# MethaneFlux.net
KiCad netlist of a schematic drawn in EAGLE
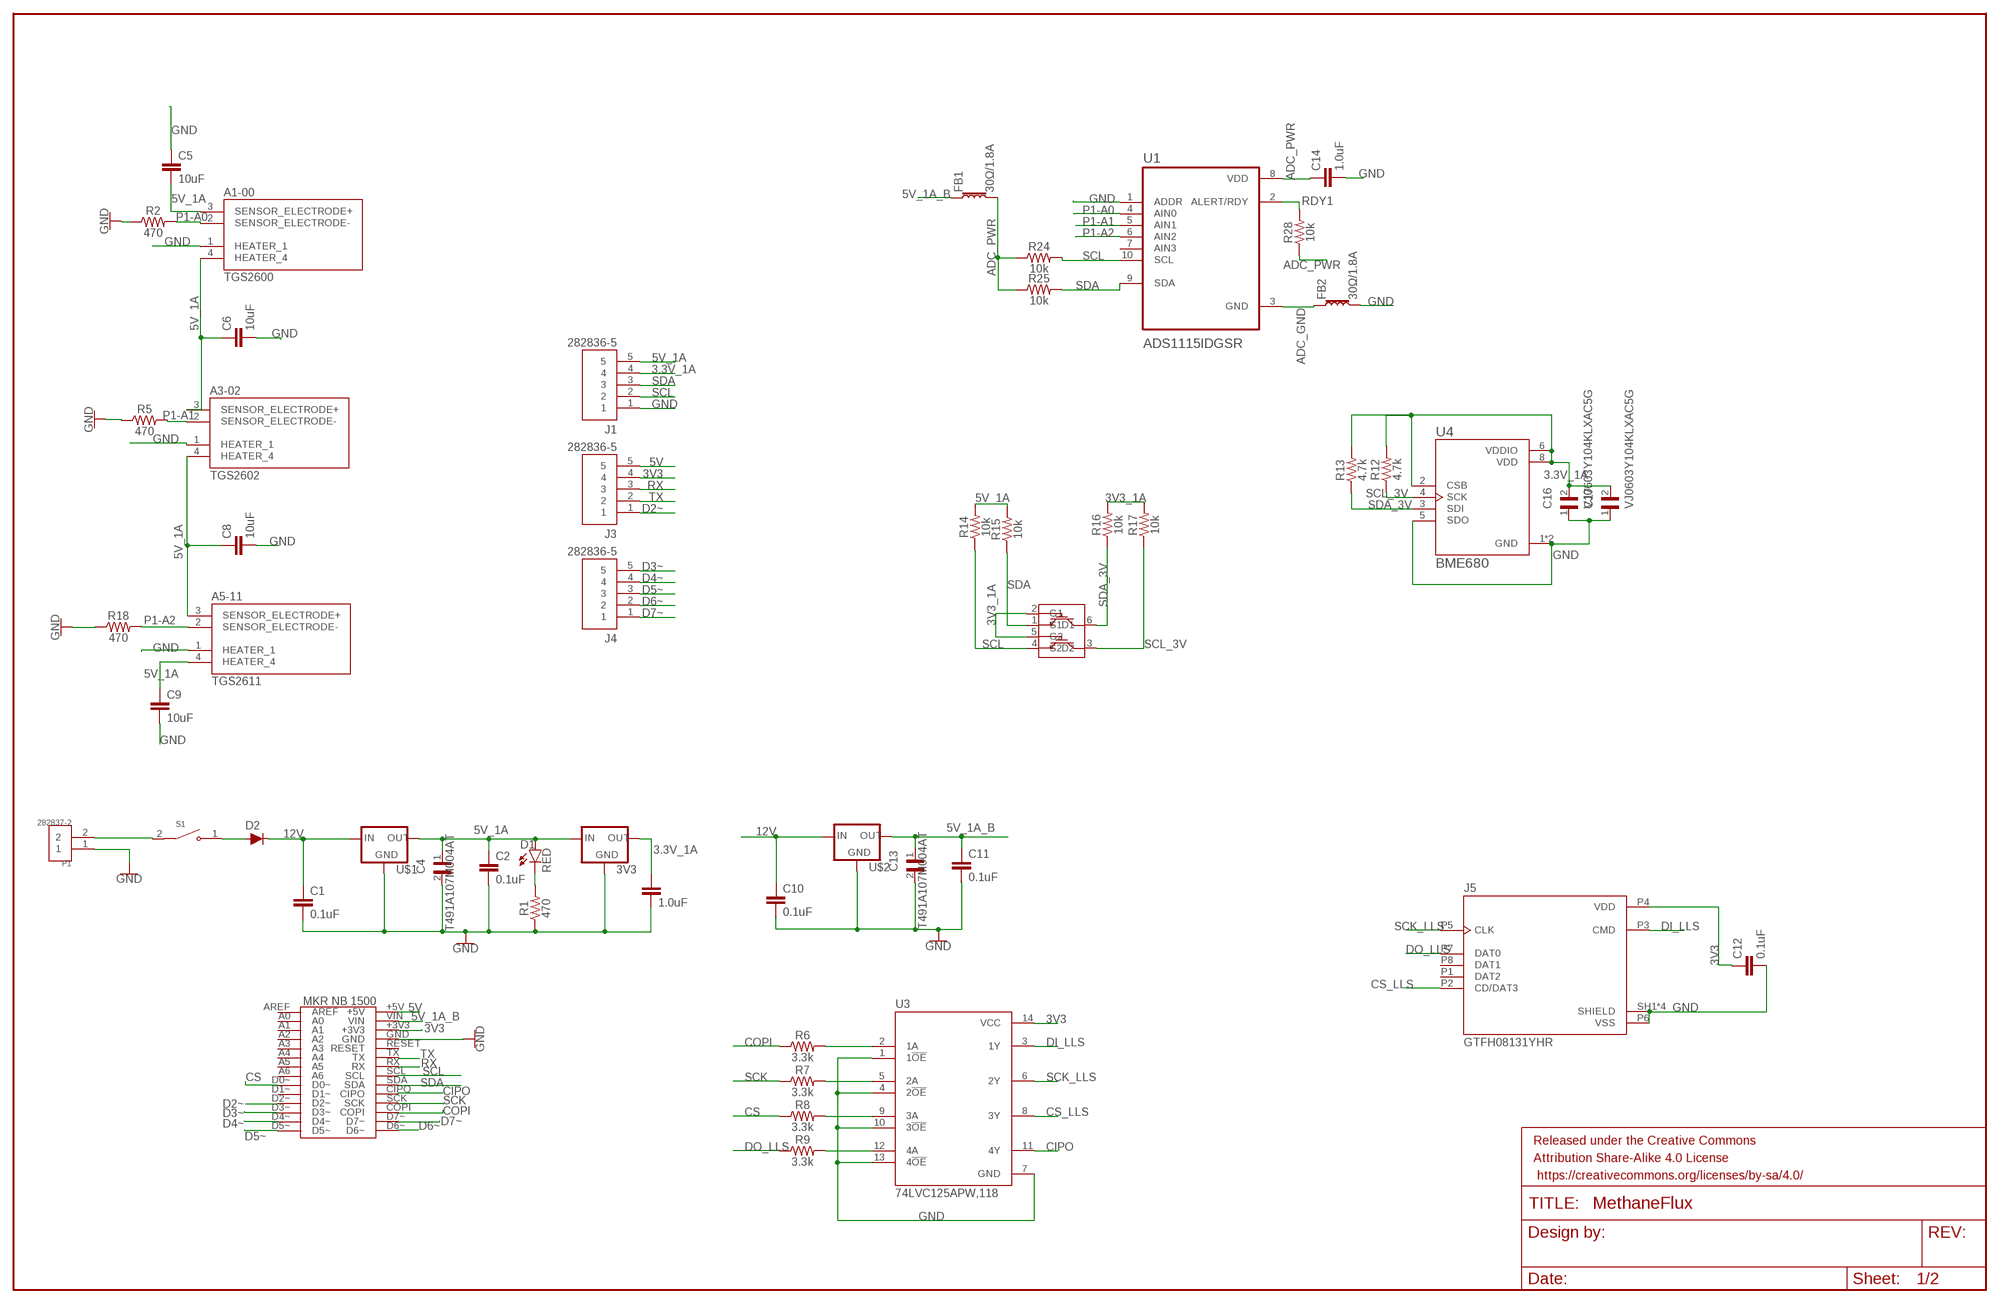
[diagram p0: schematic, sheet 1]
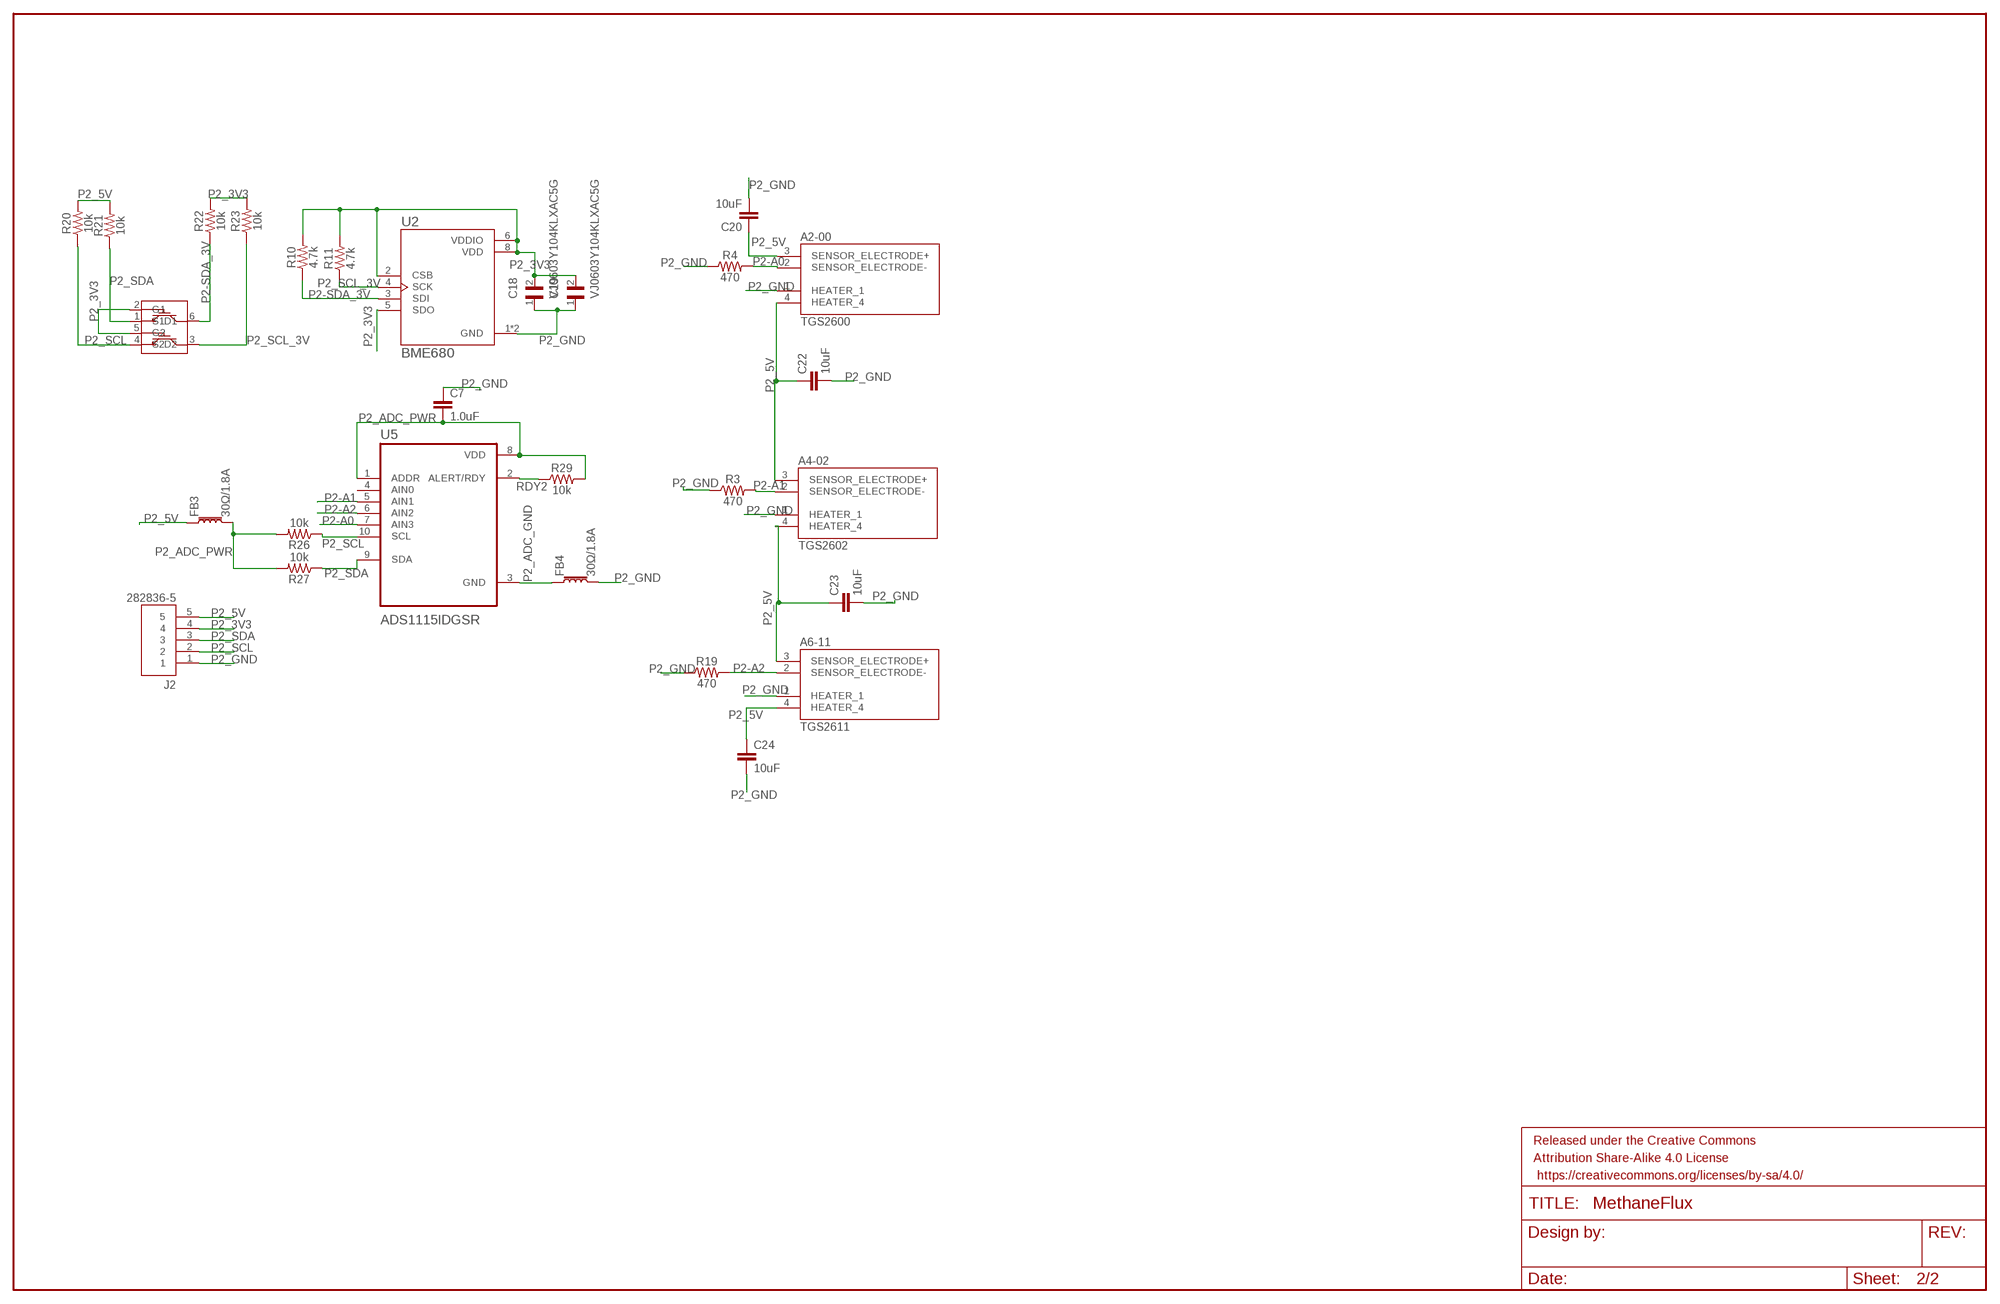
[diagram p1: schematic, sheet 2]

(export (version "E")
  (design (tool "Eeschema 10.0.6"))
  (components
    (comp (ref "3V3")
      (value "V_REG_LD1117VXXLD1117-SMD")
      (footprint "eagle-import:SOT223")
      (libsource (lib "eagle-import") (part "V_REG_LD1117VXXLD1117-SMD"))
    )
    (comp (ref "A1-00")
      (value "TGS2600")
      (footprint "eagle-import:TO255P920H830-4")
      (fields (field (name "MF") "Figaro"))
      (libsource (lib "eagle-import") (part "TGS2600"))
    )
    (comp (ref "A3-02")
      (value "TGS2602")
      (footprint "eagle-import:TGS2602")
      (libsource (lib "eagle-import") (part "TGS2602"))
    )
    (comp (ref "A5-11")
      (value "TGS2611")
      (footprint "eagle-import:TGS2611")
      (libsource (lib "eagle-import") (part "TGS2611"))
    )
    (comp (ref "C1")
      (value "0.1uF")
      (footprint "eagle-import:0603")
      (libsource (lib "eagle-import") (part "0.1UF-0603-25V-5%"))
    )
    (comp (ref "C2")
      (value "0.1uF")
      (footprint "eagle-import:0603")
      (libsource (lib "eagle-import") (part "0.1UF-0603-25V-5%"))
    )
    (comp (ref "C3")
      (value "1.0uF")
      (footprint "eagle-import:0603")
      (libsource (lib "eagle-import") (part "1.0UF-0603-16V-10%"))
    )
    (comp (ref "C4")
      (value "T491A107M004AT")
      (footprint "eagle-import:CAPC3216X110N")
      (fields (field (name "MF") "KEMET"))
      (libsource (lib "eagle-import") (part "T491A107M004AT"))
    )
    (comp (ref "C5")
      (value "10uF")
      (footprint "eagle-import:0603")
      (libsource (lib "eagle-import") (part "10UF-0603-6.3V-20%"))
    )
    (comp (ref "C6")
      (value "10uF")
      (footprint "eagle-import:0603")
      (libsource (lib "eagle-import") (part "10UF-0603-6.3V-20%"))
    )
    (comp (ref "C8")
      (value "10uF")
      (footprint "eagle-import:0603")
      (libsource (lib "eagle-import") (part "10UF-0603-6.3V-20%"))
    )
    (comp (ref "C9")
      (value "10uF")
      (footprint "eagle-import:0603")
      (libsource (lib "eagle-import") (part "10UF-0603-6.3V-20%"))
    )
    (comp (ref "C10")
      (value "0.1uF")
      (footprint "eagle-import:0603")
      (libsource (lib "eagle-import") (part "0.1UF-0603-25V-5%"))
    )
    (comp (ref "C11")
      (value "0.1uF")
      (footprint "eagle-import:0603")
      (libsource (lib "eagle-import") (part "0.1UF-0603-25V-5%"))
    )
    (comp (ref "C12")
      (value "0.1uF")
      (footprint "eagle-import:0603")
      (libsource (lib "eagle-import") (part "0.1UF-0603-25V-5%"))
    )
    (comp (ref "C13")
      (value "T491A107M004AT")
      (footprint "eagle-import:CAPC3216X110N")
      (fields (field (name "MF") "KEMET"))
      (libsource (lib "eagle-import") (part "T491A107M004AT"))
    )
    (comp (ref "C14")
      (value "1.0uF")
      (footprint "eagle-import:0603")
      (libsource (lib "eagle-import") (part "1.0UF-0603-16V-10%"))
    )
    (comp (ref "C16")
      (value "VJ0603Y104KLXAC5G")
      (footprint "eagle-import:CAPC1608X92N")
      (fields (field (name "MF") "Vishay"))
      (libsource (lib "eagle-import") (part "VJ0603Y104KLXAC5G"))
    )
    (comp (ref "C17")
      (value "VJ0603Y104KLXAC5G")
      (footprint "eagle-import:CAPC1608X92N")
      (fields (field (name "MF") "Vishay"))
      (libsource (lib "eagle-import") (part "VJ0603Y104KLXAC5G"))
    )
    (comp (ref "D1")
      (value "RED")
      (footprint "eagle-import:LED-0603")
      (libsource (lib "eagle-import") (part "LED-RED0603"))
    )
    (comp (ref "D2")
      (value "200mA/100V/1V")
      (footprint "eagle-import:DIODE-1N4148")
      (libsource (lib "eagle-import") (part "DIODE-1N4148"))
    )
    (comp (ref "FB1")
      (value "30Ω/1.8A")
      (footprint "eagle-import:0603")
      (libsource (lib "eagle-import") (part "FERRITE_BEAD-0603"))
    )
    (comp (ref "FB2")
      (value "30Ω/1.8A")
      (footprint "eagle-import:0603")
      (libsource (lib "eagle-import") (part "FERRITE_BEAD-0603"))
    )
    (comp (ref "FRAME1")
      (value "FRAME-LEDGER")
      (footprint "eagle-import:CREATIVE_COMMONS")
      (libsource (lib "eagle-import") (part "FRAME-LEDGER"))
    )
    (comp (ref "J1")
      (value "282836-5")
      (footprint "eagle-import:TE_282836-5")
      (fields (field (name "MF") "TE Connectivity"))
      (libsource (lib "eagle-import") (part "282836-5"))
    )
    (comp (ref "J3")
      (value "282836-5")
      (footprint "eagle-import:TE_282836-5")
      (fields (field (name "MF") "TE Connectivity"))
      (libsource (lib "eagle-import") (part "282836-5"))
    )
    (comp (ref "J4")
      (value "282836-5")
      (footprint "eagle-import:TE_282836-5")
      (fields (field (name "MF") "TE Connectivity"))
      (libsource (lib "eagle-import") (part "282836-5"))
    )
    (comp (ref "J5")
      (value "GTFH08131YHR")
      (footprint "eagle-import:AMPHENOL_GTFH08131YHR")
      (fields (field (name "MF") "Amphenol ICC"))
      (libsource (lib "eagle-import") (part "GTFH08131YHR"))
    )
    (comp (ref "P1")
      (value "282837-2")
      (footprint "eagle-import:TE_282837-2")
      (fields (field (name "MF") "TE Connectivity"))
      (libsource (lib "eagle-import") (part "282837-2"))
    )
    (comp (ref "R1")
      (value "470")
      (footprint "eagle-import:0603")
      (libsource (lib "eagle-import") (part "470OHM-0603-1/10W-1%"))
    )
    (comp (ref "R2")
      (value "470")
      (footprint "eagle-import:0603")
      (libsource (lib "eagle-import") (part "470OHM-0603-1/10W-1%"))
    )
    (comp (ref "R5")
      (value "470")
      (footprint "eagle-import:0603")
      (libsource (lib "eagle-import") (part "470OHM-0603-1/10W-1%"))
    )
    (comp (ref "R6")
      (value "3.3k")
      (footprint "eagle-import:0603")
      (libsource (lib "eagle-import") (part "3.3KOHM-0603-1/10W-1%"))
    )
    (comp (ref "R7")
      (value "3.3k")
      (footprint "eagle-import:0603")
      (libsource (lib "eagle-import") (part "3.3KOHM-0603-1/10W-1%"))
    )
    (comp (ref "R8")
      (value "3.3k")
      (footprint "eagle-import:0603")
      (libsource (lib "eagle-import") (part "3.3KOHM-0603-1/10W-1%"))
    )
    (comp (ref "R9")
      (value "3.3k")
      (footprint "eagle-import:0603")
      (libsource (lib "eagle-import") (part "3.3KOHM-0603-1/10W-1%"))
    )
    (comp (ref "R12")
      (value "4.7k")
      (footprint "eagle-import:0603")
      (libsource (lib "eagle-import") (part "4.7KOHM-0603-1/10W-1%"))
    )
    (comp (ref "R13")
      (value "4.7k")
      (footprint "eagle-import:0603")
      (libsource (lib "eagle-import") (part "4.7KOHM-0603-1/10W-1%"))
    )
    (comp (ref "R14")
      (value "10k")
      (footprint "eagle-import:0603")
      (libsource (lib "eagle-import") (part "10KOHM-0603-1/10W-1%"))
    )
    (comp (ref "R15")
      (value "10k")
      (footprint "eagle-import:0603")
      (libsource (lib "eagle-import") (part "10KOHM-0603-1/10W-1%"))
    )
    (comp (ref "R16")
      (value "10k")
      (footprint "eagle-import:0603")
      (libsource (lib "eagle-import") (part "10KOHM-0603-1/10W-1%"))
    )
    (comp (ref "R17")
      (value "10k")
      (footprint "eagle-import:0603")
      (libsource (lib "eagle-import") (part "10KOHM-0603-1/10W-1%"))
    )
    (comp (ref "R18")
      (value "470")
      (footprint "eagle-import:0603")
      (libsource (lib "eagle-import") (part "470OHM-0603-1/10W-1%"))
    )
    (comp (ref "R24")
      (value "10k")
      (footprint "eagle-import:0603")
      (libsource (lib "eagle-import") (part "10KOHM-0603-1/10W-1%"))
    )
    (comp (ref "R25")
      (value "10k")
      (footprint "eagle-import:0603")
      (libsource (lib "eagle-import") (part "10KOHM-0603-1/10W-1%"))
    )
    (comp (ref "R28")
      (value "10k")
      (footprint "eagle-import:0603")
      (libsource (lib "eagle-import") (part "10KOHM-0603-1/10W-1%"))
    )
    (comp (ref "S1")
      (value "RB141C1100")
      (footprint "eagle-import:SW_RB141C1100")
      (fields (field (name "MF") "E-Switch"))
      (libsource (lib "eagle-import") (part "RB141C1100"))
    )
    (comp (ref "U$1")
      (value "V_REG_LD1117VXXLD1117-SMD")
      (footprint "eagle-import:SOT223")
      (libsource (lib "eagle-import") (part "V_REG_LD1117VXXLD1117-SMD"))
    )
    (comp (ref "U$2")
      (value "V_REG_LD1117VXXLD1117-SMD")
      (footprint "eagle-import:SOT223")
      (libsource (lib "eagle-import") (part "V_REG_LD1117VXXLD1117-SMD"))
    )
    (comp (ref "U$3")
      (value "2N7002DW")
      (footprint "eagle-import:SOT363")
      (fields (field (name "MF") "onsemi"))
      (libsource (lib "eagle-import") (part "2N7002DW"))
    )
    (comp (ref "U$5")
      (value "MKRNB1500")
      (footprint "eagle-import:MRKNB1500")
      (libsource (lib "eagle-import") (part "MKRNB1500"))
    )
    (comp (ref "U1")
      (value "ADS1115IDGSR")
      (footprint "eagle-import:SOP50P490X110-10N")
      (fields (field (name "MF") "Texas Instruments"))
      (libsource (lib "eagle-import") (part "ADS1115IDGSR"))
    )
    (comp (ref "U3")
      (value "74LVC125APW,118")
      (footprint "eagle-import:IC_74LVC125APW,118")
      (fields (field (name "MF") "Nexperia USA Inc."))
      (libsource (lib "eagle-import") (part "74LVC125APW,118"))
    )
    (comp (ref "U4")
      (value "BME680")
      (footprint "eagle-import:PSON80P300X300X100-8N")
      (fields (field (name "MF") "Bosch Sensortec"))
      (libsource (lib "eagle-import") (part "BME680"))
    )
    (comp (ref "A2-00")
      (value "TGS2600")
      (footprint "eagle-import:TO255P920H830-4")
      (fields (field (name "MF") "Figaro"))
      (libsource (lib "eagle-import") (part "TGS2600"))
    )
    (comp (ref "A4-02")
      (value "TGS2602")
      (footprint "eagle-import:TGS2602")
      (libsource (lib "eagle-import") (part "TGS2602"))
    )
    (comp (ref "A6-11")
      (value "TGS2611")
      (footprint "eagle-import:TGS2611")
      (libsource (lib "eagle-import") (part "TGS2611"))
    )
    (comp (ref "C7")
      (value "1.0uF")
      (footprint "eagle-import:0603")
      (libsource (lib "eagle-import") (part "1.0UF-0603-16V-10%"))
    )
    (comp (ref "C18")
      (value "VJ0603Y104KLXAC5G")
      (footprint "eagle-import:CAPC1608X92N")
      (fields (field (name "MF") "Vishay"))
      (libsource (lib "eagle-import") (part "VJ0603Y104KLXAC5G"))
    )
    (comp (ref "C19")
      (value "VJ0603Y104KLXAC5G")
      (footprint "eagle-import:CAPC1608X92N")
      (fields (field (name "MF") "Vishay"))
      (libsource (lib "eagle-import") (part "VJ0603Y104KLXAC5G"))
    )
    (comp (ref "C20")
      (value "10uF")
      (footprint "eagle-import:0603")
      (libsource (lib "eagle-import") (part "10UF-0603-6.3V-20%"))
    )
    (comp (ref "C22")
      (value "10uF")
      (footprint "eagle-import:0603")
      (libsource (lib "eagle-import") (part "10UF-0603-6.3V-20%"))
    )
    (comp (ref "C23")
      (value "10uF")
      (footprint "eagle-import:0603")
      (libsource (lib "eagle-import") (part "10UF-0603-6.3V-20%"))
    )
    (comp (ref "C24")
      (value "10uF")
      (footprint "eagle-import:0603")
      (libsource (lib "eagle-import") (part "10UF-0603-6.3V-20%"))
    )
    (comp (ref "FB3")
      (value "30Ω/1.8A")
      (footprint "eagle-import:0603")
      (libsource (lib "eagle-import") (part "FERRITE_BEAD-0603"))
    )
    (comp (ref "FB4")
      (value "30Ω/1.8A")
      (footprint "eagle-import:0603")
      (libsource (lib "eagle-import") (part "FERRITE_BEAD-0603"))
    )
    (comp (ref "FRAME2")
      (value "FRAME-LEDGER")
      (footprint "eagle-import:CREATIVE_COMMONS")
      (libsource (lib "eagle-import") (part "FRAME-LEDGER"))
    )
    (comp (ref "J2")
      (value "282836-5")
      (footprint "eagle-import:TE_282836-5")
      (fields (field (name "MF") "TE Connectivity"))
      (libsource (lib "eagle-import") (part "282836-5"))
    )
    (comp (ref "R3")
      (value "470")
      (footprint "eagle-import:0603")
      (libsource (lib "eagle-import") (part "470OHM-0603-1/10W-1%"))
    )
    (comp (ref "R4")
      (value "470")
      (footprint "eagle-import:0603")
      (libsource (lib "eagle-import") (part "470OHM-0603-1/10W-1%"))
    )
    (comp (ref "R10")
      (value "4.7k")
      (footprint "eagle-import:0603")
      (libsource (lib "eagle-import") (part "4.7KOHM-0603-1/10W-1%"))
    )
    (comp (ref "R11")
      (value "4.7k")
      (footprint "eagle-import:0603")
      (libsource (lib "eagle-import") (part "4.7KOHM-0603-1/10W-1%"))
    )
    (comp (ref "R19")
      (value "470")
      (footprint "eagle-import:0603")
      (libsource (lib "eagle-import") (part "470OHM-0603-1/10W-1%"))
    )
    (comp (ref "R20")
      (value "10k")
      (footprint "eagle-import:0603")
      (libsource (lib "eagle-import") (part "10KOHM-0603-1/10W-1%"))
    )
    (comp (ref "R21")
      (value "10k")
      (footprint "eagle-import:0603")
      (libsource (lib "eagle-import") (part "10KOHM-0603-1/10W-1%"))
    )
    (comp (ref "R22")
      (value "10k")
      (footprint "eagle-import:0603")
      (libsource (lib "eagle-import") (part "10KOHM-0603-1/10W-1%"))
    )
    (comp (ref "R23")
      (value "10k")
      (footprint "eagle-import:0603")
      (libsource (lib "eagle-import") (part "10KOHM-0603-1/10W-1%"))
    )
    (comp (ref "R26")
      (value "10k")
      (footprint "eagle-import:0603")
      (libsource (lib "eagle-import") (part "10KOHM-0603-1/10W-1%"))
    )
    (comp (ref "R27")
      (value "10k")
      (footprint "eagle-import:0603")
      (libsource (lib "eagle-import") (part "10KOHM-0603-1/10W-1%"))
    )
    (comp (ref "R29")
      (value "10k")
      (footprint "eagle-import:0603")
      (libsource (lib "eagle-import") (part "10KOHM-0603-1/10W-1%"))
    )
    (comp (ref "U$4")
      (value "2N7002DW")
      (footprint "eagle-import:SOT363")
      (fields (field (name "MF") "onsemi"))
      (libsource (lib "eagle-import") (part "2N7002DW"))
    )
    (comp (ref "U2")
      (value "BME680")
      (footprint "eagle-import:PSON80P300X300X100-8N")
      (fields (field (name "MF") "Bosch Sensortec"))
      (libsource (lib "eagle-import") (part "BME680"))
    )
    (comp (ref "U5")
      (value "ADS1115IDGSR")
      (footprint "eagle-import:SOP50P490X110-10N")
      (fields (field (name "MF") "Texas Instruments"))
      (libsource (lib "eagle-import") (part "ADS1115IDGSR"))
    )
  )
  (nets
    (net (code "1") (name "3.3V_1A") (class "Default")
      (node (ref "3V3") (pin "2") (pinfunction "OUT_2") (pintype "passive"))
      (node (ref "C16") (pin "2") (pinfunction "2_2") (pintype "passive"))
      (node (ref "C17") (pin "2") (pinfunction "2_2") (pintype "passive"))
      (node (ref "C3") (pin "1") (pinfunction "1_1") (pintype "passive"))
      (node (ref "J1") (pin "4") (pinfunction "4_4") (pintype "passive"))
      (node (ref "R12") (pin "2") (pinfunction "2_2") (pintype "passive"))
      (node (ref "R13") (pin "2") (pinfunction "2_2") (pintype "passive"))
      (node (ref "U4") (pin "2") (pinfunction "CSB_2") (pintype "input"))
      (node (ref "U4") (pin "6") (pinfunction "VDDIO_6") (pintype "power_in"))
      (node (ref "U4") (pin "8") (pinfunction "VDD_8") (pintype "power_in"))
    )
    (net (code "2") (name "3V3") (class "Default")
      (node (ref "C12") (pin "1") (pinfunction "1_1") (pintype "passive"))
      (node (ref "J3") (pin "4") (pinfunction "4_4") (pintype "passive"))
      (node (ref "J5") (pin "P4") (pinfunction "VDD_P4") (pintype "power_in"))
      (node (ref "U$5") (pin "+3V3") (pinfunction "+3V3_+3V3") (pintype "bidirectional"))
      (node (ref "U3") (pin "14") (pinfunction "VCC_14") (pintype "power_in"))
    )
    (net (code "3") (name "3V3_1A") (class "Default")
      (node (ref "R16") (pin "2") (pinfunction "2_2") (pintype "passive"))
      (node (ref "R17") (pin "2") (pinfunction "2_2") (pintype "passive"))
      (node (ref "U$3") (pin "2") (pinfunction "G1_2") (pintype "bidirectional"))
      (node (ref "U$3") (pin "5") (pinfunction "G2_5") (pintype "bidirectional"))
    )
    (net (code "4") (name "5V") (class "Default")
      (node (ref "J3") (pin "5") (pinfunction "5_5") (pintype "passive"))
      (node (ref "U$5") (pin "+5V") (pinfunction "+5V_+5V") (pintype "bidirectional"))
    )
    (net (code "5") (name "5V_1A") (class "Default")
      (node (ref "3V3") (pin "3") (pinfunction "IN_3") (pintype "input"))
      (node (ref "A1-00") (pin "3") (pinfunction "SENSOR_ELECTRODE+_3") (pintype "passive"))
      (node (ref "A1-00") (pin "4") (pinfunction "HEATER_4_4") (pintype "passive"))
      (node (ref "A3-02") (pin "3") (pinfunction "SENSOR_ELECTRODE+_3") (pintype "passive"))
      (node (ref "A3-02") (pin "4") (pinfunction "HEATER_4_4") (pintype "passive"))
      (node (ref "A5-11") (pin "3") (pinfunction "SENSOR_ELECTRODE+_3") (pintype "passive"))
      (node (ref "A5-11") (pin "4") (pinfunction "HEATER_4_4") (pintype "passive"))
      (node (ref "C2") (pin "1") (pinfunction "1_1") (pintype "passive"))
      (node (ref "C4") (pin "1") (pinfunction "1_1") (pintype "passive"))
      (node (ref "C5") (pin "2") (pinfunction "2_2") (pintype "passive"))
      (node (ref "C6") (pin "1") (pinfunction "1_1") (pintype "passive"))
      (node (ref "C8") (pin "1") (pinfunction "1_1") (pintype "passive"))
      (node (ref "C9") (pin "1") (pinfunction "1_1") (pintype "passive"))
      (node (ref "D1") (pin "A") (pinfunction "A_A") (pintype "passive"))
      (node (ref "J1") (pin "5") (pinfunction "5_5") (pintype "passive"))
      (node (ref "R14") (pin "2") (pinfunction "2_2") (pintype "passive"))
      (node (ref "R15") (pin "2") (pinfunction "2_2") (pintype "passive"))
      (node (ref "U$1") (pin "2") (pinfunction "OUT_2") (pintype "passive"))
    )
    (net (code "6") (name "5V_1A_B") (class "Default")
      (node (ref "C11") (pin "1") (pinfunction "1_1") (pintype "passive"))
      (node (ref "C13") (pin "1") (pinfunction "1_1") (pintype "passive"))
      (node (ref "FB1") (pin "1") (pinfunction "1_1") (pintype "passive"))
      (node (ref "U$2") (pin "2") (pinfunction "OUT_2") (pintype "passive"))
      (node (ref "U$5") (pin "VIN") (pinfunction "VIN_VIN") (pintype "bidirectional"))
    )
    (net (code "7") (name "12V") (class "Default")
      (node (ref "C1") (pin "1") (pinfunction "1_1") (pintype "passive"))
      (node (ref "C10") (pin "1") (pinfunction "1_1") (pintype "passive"))
      (node (ref "D2") (pin "C") (pinfunction "C_C") (pintype "passive"))
      (node (ref "U$1") (pin "3") (pinfunction "IN_3") (pintype "input"))
      (node (ref "U$2") (pin "3") (pinfunction "IN_3") (pintype "input"))
    )
    (net (code "8") (name "ADC_GND") (class "Default")
      (node (ref "FB2") (pin "1") (pinfunction "1_1") (pintype "passive"))
      (node (ref "U1") (pin "3") (pinfunction "GND_3") (pintype "power_in"))
    )
    (net (code "9") (name "ADC_PWR") (class "Default")
      (node (ref "C14") (pin "1") (pinfunction "1_1") (pintype "passive"))
      (node (ref "FB1") (pin "2") (pinfunction "2_2") (pintype "passive"))
      (node (ref "R24") (pin "1") (pinfunction "1_1") (pintype "passive"))
      (node (ref "R25") (pin "1") (pinfunction "1_1") (pintype "passive"))
      (node (ref "R28") (pin "1") (pinfunction "1_1") (pintype "passive"))
      (node (ref "U1") (pin "8") (pinfunction "VDD_8") (pintype "power_in"))
    )
    (net (code "10") (name "CIPO") (class "Default")
      (node (ref "U$5") (pin "CIPO") (pinfunction "CIPO_CIPO") (pintype "bidirectional"))
      (node (ref "U3") (pin "11") (pinfunction "4Y_11") (pintype "output"))
    )
    (net (code "11") (name "COPI") (class "Default")
      (node (ref "R6") (pin "1") (pinfunction "1_1") (pintype "passive"))
      (node (ref "U$5") (pin "COPI") (pinfunction "COPI_COPI") (pintype "bidirectional"))
    )
    (net (code "12") (name "CS") (class "Default")
      (node (ref "R8") (pin "1") (pinfunction "1_1") (pintype "passive"))
      (node (ref "U$5") (pin "D0~") (pinfunction "D0~{}_D0~") (pintype "bidirectional"))
    )
    (net (code "13") (name "CS_LLS") (class "Default")
      (node (ref "J5") (pin "P2") (pinfunction "CD/DAT3_P2") (pintype "bidirectional"))
      (node (ref "U3") (pin "8") (pinfunction "3Y_8") (pintype "output"))
    )
    (net (code "14") (name "D2~{}") (class "Default")
      (node (ref "J3") (pin "1") (pinfunction "1_1") (pintype "passive"))
      (node (ref "U$5") (pin "D2~") (pinfunction "D2~{}_D2~") (pintype "bidirectional"))
    )
    (net (code "15") (name "D3~{}") (class "Default")
      (node (ref "J4") (pin "5") (pinfunction "5_5") (pintype "passive"))
      (node (ref "U$5") (pin "D3~") (pinfunction "D3~{}_D3~") (pintype "bidirectional"))
    )
    (net (code "16") (name "D4~{}") (class "Default")
      (node (ref "J4") (pin "4") (pinfunction "4_4") (pintype "passive"))
      (node (ref "U$5") (pin "D4~") (pinfunction "D4~{}_D4~") (pintype "bidirectional"))
    )
    (net (code "17") (name "D5~{}") (class "Default")
      (node (ref "J4") (pin "3") (pinfunction "3_3") (pintype "passive"))
      (node (ref "U$5") (pin "D5~") (pinfunction "D5~{}_D5~") (pintype "bidirectional"))
    )
    (net (code "18") (name "D6~{}") (class "Default")
      (node (ref "J4") (pin "2") (pinfunction "2_2") (pintype "passive"))
      (node (ref "U$5") (pin "D6~") (pinfunction "D6~{}_D6~") (pintype "bidirectional"))
    )
    (net (code "19") (name "D7~{}") (class "Default")
      (node (ref "J4") (pin "1") (pinfunction "1_1") (pintype "passive"))
      (node (ref "U$5") (pin "D7~") (pinfunction "D7~{}_D7~") (pintype "bidirectional"))
    )
    (net (code "20") (name "DI_LLS") (class "Default")
      (node (ref "J5") (pin "P3") (pinfunction "CMD_P3") (pintype "bidirectional"))
      (node (ref "U3") (pin "3") (pinfunction "1Y_3") (pintype "output"))
    )
    (net (code "21") (name "DO_LLS") (class "Default")
      (node (ref "J5") (pin "P7") (pinfunction "DAT0_P7") (pintype "bidirectional"))
      (node (ref "R9") (pin "1") (pinfunction "1_1") (pintype "passive"))
    )
    (net (code "22") (name "GND") (class "Default")
      (node (ref "3V3") (pin "1") (pinfunction "GND_1") (pintype "input"))
      (node (ref "A1-00") (pin "1") (pinfunction "HEATER_1_1") (pintype "passive"))
      (node (ref "A3-02") (pin "1") (pinfunction "HEATER_1_1") (pintype "passive"))
      (node (ref "A5-11") (pin "1") (pinfunction "HEATER_1_1") (pintype "passive"))
      (node (ref "C1") (pin "2") (pinfunction "2_2") (pintype "passive"))
      (node (ref "C10") (pin "2") (pinfunction "2_2") (pintype "passive"))
      (node (ref "C11") (pin "2") (pinfunction "2_2") (pintype "passive"))
      (node (ref "C12") (pin "2") (pinfunction "2_2") (pintype "passive"))
      (node (ref "C13") (pin "2") (pinfunction "2_2") (pintype "passive"))
      (node (ref "C14") (pin "2") (pinfunction "2_2") (pintype "passive"))
      (node (ref "C16") (pin "1") (pinfunction "1_1") (pintype "passive"))
      (node (ref "C17") (pin "1") (pinfunction "1_1") (pintype "passive"))
      (node (ref "C2") (pin "2") (pinfunction "2_2") (pintype "passive"))
      (node (ref "C3") (pin "2") (pinfunction "2_2") (pintype "passive"))
      (node (ref "C4") (pin "2") (pinfunction "2_2") (pintype "passive"))
      (node (ref "C5") (pin "1") (pinfunction "1_1") (pintype "passive"))
      (node (ref "C6") (pin "2") (pinfunction "2_2") (pintype "passive"))
      (node (ref "C8") (pin "2") (pinfunction "2_2") (pintype "passive"))
      (node (ref "C9") (pin "2") (pinfunction "2_2") (pintype "passive"))
      (node (ref "FB2") (pin "2") (pinfunction "2_2") (pintype "passive"))
      (node (ref "J1") (pin "1") (pinfunction "1_1") (pintype "passive"))
      (node (ref "J5") (pin "P6") (pinfunction "VSS_P6") (pintype "power_in"))
      (node (ref "J5") (pin "SH1") (pinfunction "SHIELD_SH1") (pintype "power_in"))
      (node (ref "J5") (pin "SH2") (pinfunction "SHIELD_SH2") (pintype "power_in"))
      (node (ref "J5") (pin "SH3") (pinfunction "SHIELD_SH3") (pintype "power_in"))
      (node (ref "J5") (pin "SH4") (pinfunction "SHIELD_SH4") (pintype "power_in"))
      (node (ref "P1") (pin "1") (pinfunction "1_1") (pintype "passive"))
      (node (ref "R1") (pin "1") (pinfunction "1_1") (pintype "passive"))
      (node (ref "R18") (pin "1") (pinfunction "1_1") (pintype "passive"))
      (node (ref "R2") (pin "1") (pinfunction "1_1") (pintype "passive"))
      (node (ref "R5") (pin "1") (pinfunction "1_1") (pintype "passive"))
      (node (ref "U$1") (pin "1") (pinfunction "GND_1") (pintype "input"))
      (node (ref "U$2") (pin "1") (pinfunction "GND_1") (pintype "input"))
      (node (ref "U$5") (pin "GND") (pinfunction "GND_GND") (pintype "bidirectional"))
      (node (ref "U1") (pin "1") (pinfunction "ADDR_1") (pintype "input"))
      (node (ref "U3") (pin "1") (pinfunction "1~{OE}_1") (pintype "input"))
      (node (ref "U3") (pin "10") (pinfunction "3~{OE}_10") (pintype "input"))
      (node (ref "U3") (pin "13") (pinfunction "4~{OE}_13") (pintype "input"))
      (node (ref "U3") (pin "4") (pinfunction "2~{OE}_4") (pintype "input"))
      (node (ref "U3") (pin "7") (pinfunction "GND_7") (pintype "power_in"))
      (node (ref "U4") (pin "1") (pinfunction "GND_1") (pintype "power_in"))
      (node (ref "U4") (pin "5") (pinfunction "SDO_5") (pintype "bidirectional"))
      (node (ref "U4") (pin "7") (pinfunction "GND_7") (pintype "power_in"))
    )
    (net (code "23") (name "Net-(D1-PadC)") (class "Default")
      (node (ref "D1") (pin "C") (pinfunction "C_C") (pintype "passive"))
      (node (ref "R1") (pin "2") (pinfunction "2_2") (pintype "passive"))
    )
    (net (code "24") (name "Net-(D2-PadA)") (class "Default")
      (node (ref "D2") (pin "A") (pinfunction "A_A") (pintype "passive"))
      (node (ref "S1") (pin "1") (pinfunction "1_1") (pintype "passive"))
    )
    (net (code "25") (name "Net-(P1-Pad2)") (class "Default")
      (node (ref "P1") (pin "2") (pinfunction "2_2") (pintype "passive"))
      (node (ref "S1") (pin "2") (pinfunction "2_2") (pintype "passive"))
    )
    (net (code "26") (name "Net-(U3-1A)") (class "Default")
      (node (ref "R6") (pin "2") (pinfunction "2_2") (pintype "passive"))
      (node (ref "U3") (pin "2") (pinfunction "1A_2") (pintype "input"))
    )
    (net (code "27") (name "Net-(U3-2A)") (class "Default")
      (node (ref "R7") (pin "2") (pinfunction "2_2") (pintype "passive"))
      (node (ref "U3") (pin "5") (pinfunction "2A_5") (pintype "input"))
    )
    (net (code "28") (name "Net-(U3-3A)") (class "Default")
      (node (ref "R8") (pin "2") (pinfunction "2_2") (pintype "passive"))
      (node (ref "U3") (pin "9") (pinfunction "3A_9") (pintype "input"))
    )
    (net (code "29") (name "Net-(U3-4A)") (class "Default")
      (node (ref "R9") (pin "2") (pinfunction "2_2") (pintype "passive"))
      (node (ref "U3") (pin "12") (pinfunction "4A_12") (pintype "input"))
    )
    (net (code "30") (name "P1-A0") (class "Default")
      (node (ref "A1-00") (pin "2") (pinfunction "SENSOR_ELECTRODE-_2") (pintype "passive"))
      (node (ref "R2") (pin "2") (pinfunction "2_2") (pintype "passive"))
      (node (ref "U1") (pin "4") (pinfunction "AIN0_4") (pintype "input"))
    )
    (net (code "31") (name "P1-A1") (class "Default")
      (node (ref "A3-02") (pin "2") (pinfunction "SENSOR_ELECTRODE-_2") (pintype "passive"))
      (node (ref "R5") (pin "2") (pinfunction "2_2") (pintype "passive"))
      (node (ref "U1") (pin "5") (pinfunction "AIN1_5") (pintype "input"))
    )
    (net (code "32") (name "P1-A2") (class "Default")
      (node (ref "A5-11") (pin "2") (pinfunction "SENSOR_ELECTRODE-_2") (pintype "passive"))
      (node (ref "R18") (pin "2") (pinfunction "2_2") (pintype "passive"))
      (node (ref "U1") (pin "6") (pinfunction "AIN2_6") (pintype "input"))
    )
    (net (code "33") (name "P2-A0") (class "Default")
      (node (ref "A2-00") (pin "2") (pinfunction "SENSOR_ELECTRODE-_2") (pintype "passive"))
      (node (ref "R4") (pin "2") (pinfunction "2_2") (pintype "passive"))
      (node (ref "U5") (pin "7") (pinfunction "AIN3_7") (pintype "input"))
    )
    (net (code "34") (name "P2-A1") (class "Default")
      (node (ref "A4-02") (pin "2") (pinfunction "SENSOR_ELECTRODE-_2") (pintype "passive"))
      (node (ref "R3") (pin "2") (pinfunction "2_2") (pintype "passive"))
      (node (ref "U5") (pin "5") (pinfunction "AIN1_5") (pintype "input"))
    )
    (net (code "35") (name "P2-A2") (class "Default")
      (node (ref "A6-11") (pin "2") (pinfunction "SENSOR_ELECTRODE-_2") (pintype "passive"))
      (node (ref "R19") (pin "2") (pinfunction "2_2") (pintype "passive"))
      (node (ref "U5") (pin "6") (pinfunction "AIN2_6") (pintype "input"))
    )
    (net (code "36") (name "P2-SDA_3V") (class "Default")
      (node (ref "R10") (pin "1") (pinfunction "1_1") (pintype "passive"))
      (node (ref "R22") (pin "1") (pinfunction "1_1") (pintype "passive"))
      (node (ref "U$4") (pin "6") (pinfunction "D1_6") (pintype "bidirectional"))
      (node (ref "U2") (pin "3") (pinfunction "SDI_3") (pintype "bidirectional"))
    )
    (net (code "37") (name "P2_3V3") (class "Default")
      (node (ref "C18") (pin "2") (pinfunction "2_2") (pintype "passive"))
      (node (ref "C19") (pin "2") (pinfunction "2_2") (pintype "passive"))
      (node (ref "J2") (pin "4") (pinfunction "4_4") (pintype "passive"))
      (node (ref "R10") (pin "2") (pinfunction "2_2") (pintype "passive"))
      (node (ref "R11") (pin "2") (pinfunction "2_2") (pintype "passive"))
      (node (ref "R22") (pin "2") (pinfunction "2_2") (pintype "passive"))
      (node (ref "R23") (pin "2") (pinfunction "2_2") (pintype "passive"))
      (node (ref "U$4") (pin "2") (pinfunction "G1_2") (pintype "bidirectional"))
      (node (ref "U$4") (pin "5") (pinfunction "G2_5") (pintype "bidirectional"))
      (node (ref "U2") (pin "2") (pinfunction "CSB_2") (pintype "input"))
      (node (ref "U2") (pin "5") (pinfunction "SDO_5") (pintype "bidirectional"))
      (node (ref "U2") (pin "6") (pinfunction "VDDIO_6") (pintype "power_in"))
      (node (ref "U2") (pin "8") (pinfunction "VDD_8") (pintype "power_in"))
    )
    (net (code "38") (name "P2_5V") (class "Default")
      (node (ref "A2-00") (pin "3") (pinfunction "SENSOR_ELECTRODE+_3") (pintype "passive"))
      (node (ref "A2-00") (pin "4") (pinfunction "HEATER_4_4") (pintype "passive"))
      (node (ref "A4-02") (pin "3") (pinfunction "SENSOR_ELECTRODE+_3") (pintype "passive"))
      (node (ref "A4-02") (pin "4") (pinfunction "HEATER_4_4") (pintype "passive"))
      (node (ref "A6-11") (pin "3") (pinfunction "SENSOR_ELECTRODE+_3") (pintype "passive"))
      (node (ref "A6-11") (pin "4") (pinfunction "HEATER_4_4") (pintype "passive"))
      (node (ref "C20") (pin "1") (pinfunction "1_1") (pintype "passive"))
      (node (ref "C22") (pin "1") (pinfunction "1_1") (pintype "passive"))
      (node (ref "C23") (pin "1") (pinfunction "1_1") (pintype "passive"))
      (node (ref "C24") (pin "1") (pinfunction "1_1") (pintype "passive"))
      (node (ref "FB3") (pin "1") (pinfunction "1_1") (pintype "passive"))
      (node (ref "J2") (pin "5") (pinfunction "5_5") (pintype "passive"))
      (node (ref "R20") (pin "2") (pinfunction "2_2") (pintype "passive"))
      (node (ref "R21") (pin "2") (pinfunction "2_2") (pintype "passive"))
    )
    (net (code "39") (name "P2_ADC_GND") (class "Default")
      (node (ref "FB4") (pin "1") (pinfunction "1_1") (pintype "passive"))
      (node (ref "U5") (pin "3") (pinfunction "GND_3") (pintype "power_in"))
    )
    (net (code "40") (name "P2_ADC_PWR") (class "Default")
      (node (ref "C7") (pin "2") (pinfunction "2_2") (pintype "passive"))
      (node (ref "FB3") (pin "2") (pinfunction "2_2") (pintype "passive"))
      (node (ref "R26") (pin "2") (pinfunction "2_2") (pintype "passive"))
      (node (ref "R27") (pin "2") (pinfunction "2_2") (pintype "passive"))
      (node (ref "R29") (pin "2") (pinfunction "2_2") (pintype "passive"))
      (node (ref "U5") (pin "1") (pinfunction "ADDR_1") (pintype "input"))
      (node (ref "U5") (pin "8") (pinfunction "VDD_8") (pintype "power_in"))
    )
    (net (code "41") (name "P2_GND") (class "Default")
      (node (ref "A2-00") (pin "1") (pinfunction "HEATER_1_1") (pintype "passive"))
      (node (ref "A4-02") (pin "1") (pinfunction "HEATER_1_1") (pintype "passive"))
      (node (ref "A6-11") (pin "1") (pinfunction "HEATER_1_1") (pintype "passive"))
      (node (ref "C18") (pin "1") (pinfunction "1_1") (pintype "passive"))
      (node (ref "C19") (pin "1") (pinfunction "1_1") (pintype "passive"))
      (node (ref "C20") (pin "2") (pinfunction "2_2") (pintype "passive"))
      (node (ref "C22") (pin "2") (pinfunction "2_2") (pintype "passive"))
      (node (ref "C23") (pin "2") (pinfunction "2_2") (pintype "passive"))
      (node (ref "C24") (pin "2") (pinfunction "2_2") (pintype "passive"))
      (node (ref "C7") (pin "1") (pinfunction "1_1") (pintype "passive"))
      (node (ref "FB4") (pin "2") (pinfunction "2_2") (pintype "passive"))
      (node (ref "J2") (pin "1") (pinfunction "1_1") (pintype "passive"))
      (node (ref "R19") (pin "1") (pinfunction "1_1") (pintype "passive"))
      (node (ref "R3") (pin "1") (pinfunction "1_1") (pintype "passive"))
      (node (ref "R4") (pin "1") (pinfunction "1_1") (pintype "passive"))
      (node (ref "U2") (pin "1") (pinfunction "GND_1") (pintype "power_in"))
      (node (ref "U2") (pin "7") (pinfunction "GND_7") (pintype "power_in"))
    )
    (net (code "42") (name "P2_SCL") (class "Default")
      (node (ref "J2") (pin "2") (pinfunction "2_2") (pintype "passive"))
      (node (ref "R20") (pin "1") (pinfunction "1_1") (pintype "passive"))
      (node (ref "R26") (pin "1") (pinfunction "1_1") (pintype "passive"))
      (node (ref "U$4") (pin "4") (pinfunction "S2_4") (pintype "bidirectional"))
      (node (ref "U5") (pin "10") (pinfunction "SCL_10") (pintype "input"))
    )
    (net (code "43") (name "P2_SCL_3V") (class "Default")
      (node (ref "R11") (pin "1") (pinfunction "1_1") (pintype "passive"))
      (node (ref "R23") (pin "1") (pinfunction "1_1") (pintype "passive"))
      (node (ref "U$4") (pin "3") (pinfunction "D2_3") (pintype "bidirectional"))
      (node (ref "U2") (pin "4") (pinfunction "SCK_4") (pintype "input"))
    )
    (net (code "44") (name "P2_SDA") (class "Default")
      (node (ref "J2") (pin "3") (pinfunction "3_3") (pintype "passive"))
      (node (ref "R21") (pin "1") (pinfunction "1_1") (pintype "passive"))
      (node (ref "R27") (pin "1") (pinfunction "1_1") (pintype "passive"))
      (node (ref "U$4") (pin "1") (pinfunction "S1_1") (pintype "bidirectional"))
      (node (ref "U5") (pin "9") (pinfunction "SDA_9") (pintype "bidirectional"))
    )
    (net (code "45") (name "RDY1") (class "Default")
      (node (ref "R28") (pin "2") (pinfunction "2_2") (pintype "passive"))
      (node (ref "U1") (pin "2") (pinfunction "ALERT/RDY_2") (pintype "output"))
    )
    (net (code "46") (name "RDY2") (class "Default")
      (node (ref "R29") (pin "1") (pinfunction "1_1") (pintype "passive"))
      (node (ref "U5") (pin "2") (pinfunction "ALERT/RDY_2") (pintype "output"))
    )
    (net (code "47") (name "RX") (class "Default")
      (node (ref "J3") (pin "3") (pinfunction "3_3") (pintype "passive"))
      (node (ref "U$5") (pin "RX") (pinfunction "RX_RX") (pintype "bidirectional"))
    )
    (net (code "48") (name "SCK") (class "Default")
      (node (ref "R7") (pin "1") (pinfunction "1_1") (pintype "passive"))
      (node (ref "U$5") (pin "SCK") (pinfunction "SCK_SCK") (pintype "bidirectional"))
    )
    (net (code "49") (name "SCK_LLS") (class "Default")
      (node (ref "J5") (pin "P5") (pinfunction "CLK_P5") (pintype "bidirectional"))
      (node (ref "U3") (pin "6") (pinfunction "2Y_6") (pintype "output"))
    )
    (net (code "50") (name "SCL") (class "Default")
      (node (ref "J1") (pin "2") (pinfunction "2_2") (pintype "passive"))
      (node (ref "R14") (pin "1") (pinfunction "1_1") (pintype "passive"))
      (node (ref "R24") (pin "2") (pinfunction "2_2") (pintype "passive"))
      (node (ref "U$3") (pin "4") (pinfunction "S2_4") (pintype "bidirectional"))
      (node (ref "U$5") (pin "SCL") (pinfunction "SCL_SCL") (pintype "bidirectional"))
      (node (ref "U1") (pin "10") (pinfunction "SCL_10") (pintype "input"))
    )
    (net (code "51") (name "SCL_3V") (class "Default")
      (node (ref "R12") (pin "1") (pinfunction "1_1") (pintype "passive"))
      (node (ref "R17") (pin "1") (pinfunction "1_1") (pintype "passive"))
      (node (ref "U$3") (pin "3") (pinfunction "D2_3") (pintype "bidirectional"))
      (node (ref "U4") (pin "4") (pinfunction "SCK_4") (pintype "input"))
    )
    (net (code "52") (name "SDA") (class "Default")
      (node (ref "J1") (pin "3") (pinfunction "3_3") (pintype "passive"))
      (node (ref "R15") (pin "1") (pinfunction "1_1") (pintype "passive"))
      (node (ref "R25") (pin "2") (pinfunction "2_2") (pintype "passive"))
      (node (ref "U$3") (pin "1") (pinfunction "S1_1") (pintype "bidirectional"))
      (node (ref "U$5") (pin "SDA") (pinfunction "SDA_SDA") (pintype "bidirectional"))
      (node (ref "U1") (pin "9") (pinfunction "SDA_9") (pintype "bidirectional"))
    )
    (net (code "53") (name "SDA_3V") (class "Default")
      (node (ref "R13") (pin "1") (pinfunction "1_1") (pintype "passive"))
      (node (ref "R16") (pin "1") (pinfunction "1_1") (pintype "passive"))
      (node (ref "U$3") (pin "6") (pinfunction "D1_6") (pintype "bidirectional"))
      (node (ref "U4") (pin "3") (pinfunction "SDI_3") (pintype "bidirectional"))
    )
    (net (code "54") (name "TX") (class "Default")
      (node (ref "J3") (pin "2") (pinfunction "2_2") (pintype "passive"))
      (node (ref "U$5") (pin "TX") (pinfunction "TX_TX") (pintype "bidirectional"))
    )
    (net (code "55") (name "unconnected-(J5-DAT1-PadP8)") (class "Default")
      (node (ref "J5") (pin "P8") (pinfunction "DAT1_P8") (pintype "bidirectional"))
    )
    (net (code "56") (name "unconnected-(J5-DAT2-PadP1)") (class "Default")
      (node (ref "J5") (pin "P1") (pinfunction "DAT2_P1") (pintype "bidirectional"))
    )
    (net (code "57") (name "unconnected-(U$5-D1~{}-PadD1~)") (class "Default")
      (node (ref "U$5") (pin "D1~") (pinfunction "D1~{}_D1~") (pintype "bidirectional"))
    )
    (net (code "58") (name "unconnected-(U$5-PadA0)") (class "Default")
      (node (ref "U$5") (pin "A0") (pinfunction "A0_A0") (pintype "bidirectional"))
    )
    (net (code "59") (name "unconnected-(U$5-PadA1)") (class "Default")
      (node (ref "U$5") (pin "A1") (pinfunction "A1_A1") (pintype "bidirectional"))
    )
    (net (code "60") (name "unconnected-(U$5-PadA2)") (class "Default")
      (node (ref "U$5") (pin "A2") (pinfunction "A2_A2") (pintype "bidirectional"))
    )
    (net (code "61") (name "unconnected-(U$5-PadA3)") (class "Default")
      (node (ref "U$5") (pin "A3") (pinfunction "A3_A3") (pintype "bidirectional"))
    )
    (net (code "62") (name "unconnected-(U$5-PadA4)") (class "Default")
      (node (ref "U$5") (pin "A4") (pinfunction "A4_A4") (pintype "bidirectional"))
    )
    (net (code "63") (name "unconnected-(U$5-PadA5)") (class "Default")
      (node (ref "U$5") (pin "A5") (pinfunction "A5_A5") (pintype "bidirectional"))
    )
    (net (code "64") (name "unconnected-(U$5-PadA6)") (class "Default")
      (node (ref "U$5") (pin "A6") (pinfunction "A6_A6") (pintype "bidirectional"))
    )
    (net (code "65") (name "unconnected-(U$5-PadAREF)") (class "Default")
      (node (ref "U$5") (pin "AREF") (pinfunction "AREF_AREF") (pintype "bidirectional"))
    )
    (net (code "66") (name "unconnected-(U$5-PadRESET)") (class "Default")
      (node (ref "U$5") (pin "RESET") (pinfunction "RESET_RESET") (pintype "bidirectional"))
    )
    (net (code "67") (name "unconnected-(U1-AIN3-Pad7)") (class "Default")
      (node (ref "U1") (pin "7") (pinfunction "AIN3_7") (pintype "input"))
    )
    (net (code "68") (name "unconnected-(U5-AIN0-Pad4)") (class "Default")
      (node (ref "U5") (pin "4") (pinfunction "AIN0_4") (pintype "input"))
    )
  )
)
